# filter_rev2.net
KiCad netlist of a schematic drawn in EAGLE
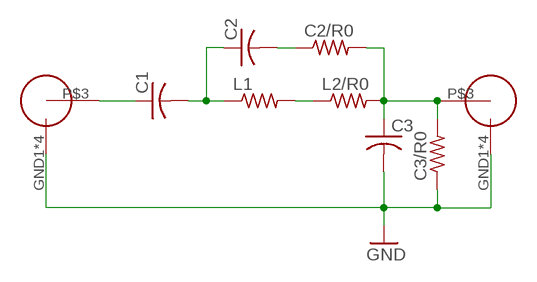
[diagram p0: schematic, sheet 1]

(export (version "E")
  (design (tool "Eeschema 10.0.6"))
  (components
    (comp (ref "C1")
      (value "C-USC0603")
      (footprint "eagle-import:C0603")
      (libsource (lib "eagle-import") (part "C-USC0603"))
    )
    (comp (ref "C2")
      (value "C-USC0603")
      (footprint "eagle-import:C0603")
      (libsource (lib "eagle-import") (part "C-USC0603"))
    )
    (comp (ref "C2/R0")
      (value "R-US_R0603")
      (footprint "eagle-import:R0603")
      (libsource (lib "eagle-import") (part "R-US_R0603"))
    )
    (comp (ref "C3")
      (value "C-USC0603")
      (footprint "eagle-import:C0603")
      (libsource (lib "eagle-import") (part "C-USC0603"))
    )
    (comp (ref "C3/R0")
      (value "R-US_R0603")
      (footprint "eagle-import:R0603")
      (libsource (lib "eagle-import") (part "R-US_R0603"))
    )
    (comp (ref "L1")
      (value "R-US_R0603")
      (footprint "eagle-import:R0603")
      (libsource (lib "eagle-import") (part "R-US_R0603"))
    )
    (comp (ref "L2/R0")
      (value "R-US_R0603")
      (footprint "eagle-import:R0603")
      (libsource (lib "eagle-import") (part "R-US_R0603"))
    )
    (comp (ref "U$1")
      (value "SMAJ716-ND")
      (footprint "eagle-import:SMAJ716-ND")
      (libsource (lib "eagle-import") (part "SMAJ716-ND"))
    )
    (comp (ref "U$2")
      (value "SMAJ716-ND")
      (footprint "eagle-import:SMAJ716-ND")
      (libsource (lib "eagle-import") (part "SMAJ716-ND"))
    )
  )
  (nets
    (net (code "1") (name "GND") (class "Default")
      (node (ref "C3") (pin "2") (pinfunction "2_2") (pintype "passive"))
      (node (ref "C3/R0") (pin "1") (pinfunction "1_1") (pintype "passive"))
      (node (ref "U$1") (pin "GND1") (pinfunction "OUTERCONDUCTOR_GND1") (pintype "bidirectional"))
      (node (ref "U$1") (pin "GND2") (pinfunction "OUTERCONDUCTOR_GND2") (pintype "bidirectional"))
      (node (ref "U$1") (pin "GND3") (pinfunction "OUTERCONDUCTOR_GND3") (pintype "bidirectional"))
      (node (ref "U$1") (pin "GND4") (pinfunction "OUTERCONDUCTOR_GND4") (pintype "bidirectional"))
      (node (ref "U$2") (pin "GND1") (pinfunction "OUTERCONDUCTOR_GND1") (pintype "bidirectional"))
      (node (ref "U$2") (pin "GND2") (pinfunction "OUTERCONDUCTOR_GND2") (pintype "bidirectional"))
      (node (ref "U$2") (pin "GND3") (pinfunction "OUTERCONDUCTOR_GND3") (pintype "bidirectional"))
      (node (ref "U$2") (pin "GND4") (pinfunction "OUTERCONDUCTOR_GND4") (pintype "bidirectional"))
    )
    (net (code "2") (name "Net-(C1-Pad2)") (class "Default")
      (node (ref "C1") (pin "2") (pinfunction "2_2") (pintype "passive"))
      (node (ref "C2") (pin "1") (pinfunction "1_1") (pintype "passive"))
      (node (ref "L1") (pin "1") (pinfunction "1_1") (pintype "passive"))
    )
    (net (code "3") (name "Net-(C2-Pad2)") (class "Default")
      (node (ref "C2") (pin "2") (pinfunction "2_2") (pintype "passive"))
      (node (ref "C2/R0") (pin "1") (pinfunction "1_1") (pintype "passive"))
    )
    (net (code "4") (name "Net-(L1-Pad2)") (class "Default")
      (node (ref "L1") (pin "2") (pinfunction "2_2") (pintype "passive"))
      (node (ref "L2/R0") (pin "1") (pinfunction "1_1") (pintype "passive"))
    )
    (net (code "5") (name "Net-(U$1-CENTERCONDUCTOR)") (class "Default")
      (node (ref "C1") (pin "1") (pinfunction "1_1") (pintype "passive"))
      (node (ref "U$1") (pin "P$3") (pinfunction "CENTERCONDUCTOR_P$3") (pintype "bidirectional"))
    )
    (net (code "6") (name "Net-(U$2-CENTERCONDUCTOR)") (class "Default")
      (node (ref "C2/R0") (pin "2") (pinfunction "2_2") (pintype "passive"))
      (node (ref "C3") (pin "1") (pinfunction "1_1") (pintype "passive"))
      (node (ref "C3/R0") (pin "2") (pinfunction "2_2") (pintype "passive"))
      (node (ref "L2/R0") (pin "2") (pinfunction "2_2") (pintype "passive"))
      (node (ref "U$2") (pin "P$3") (pinfunction "CENTERCONDUCTOR_P$3") (pintype "bidirectional"))
    )
  )
)
